# node.net
KiCad netlist of a schematic drawn in EAGLE
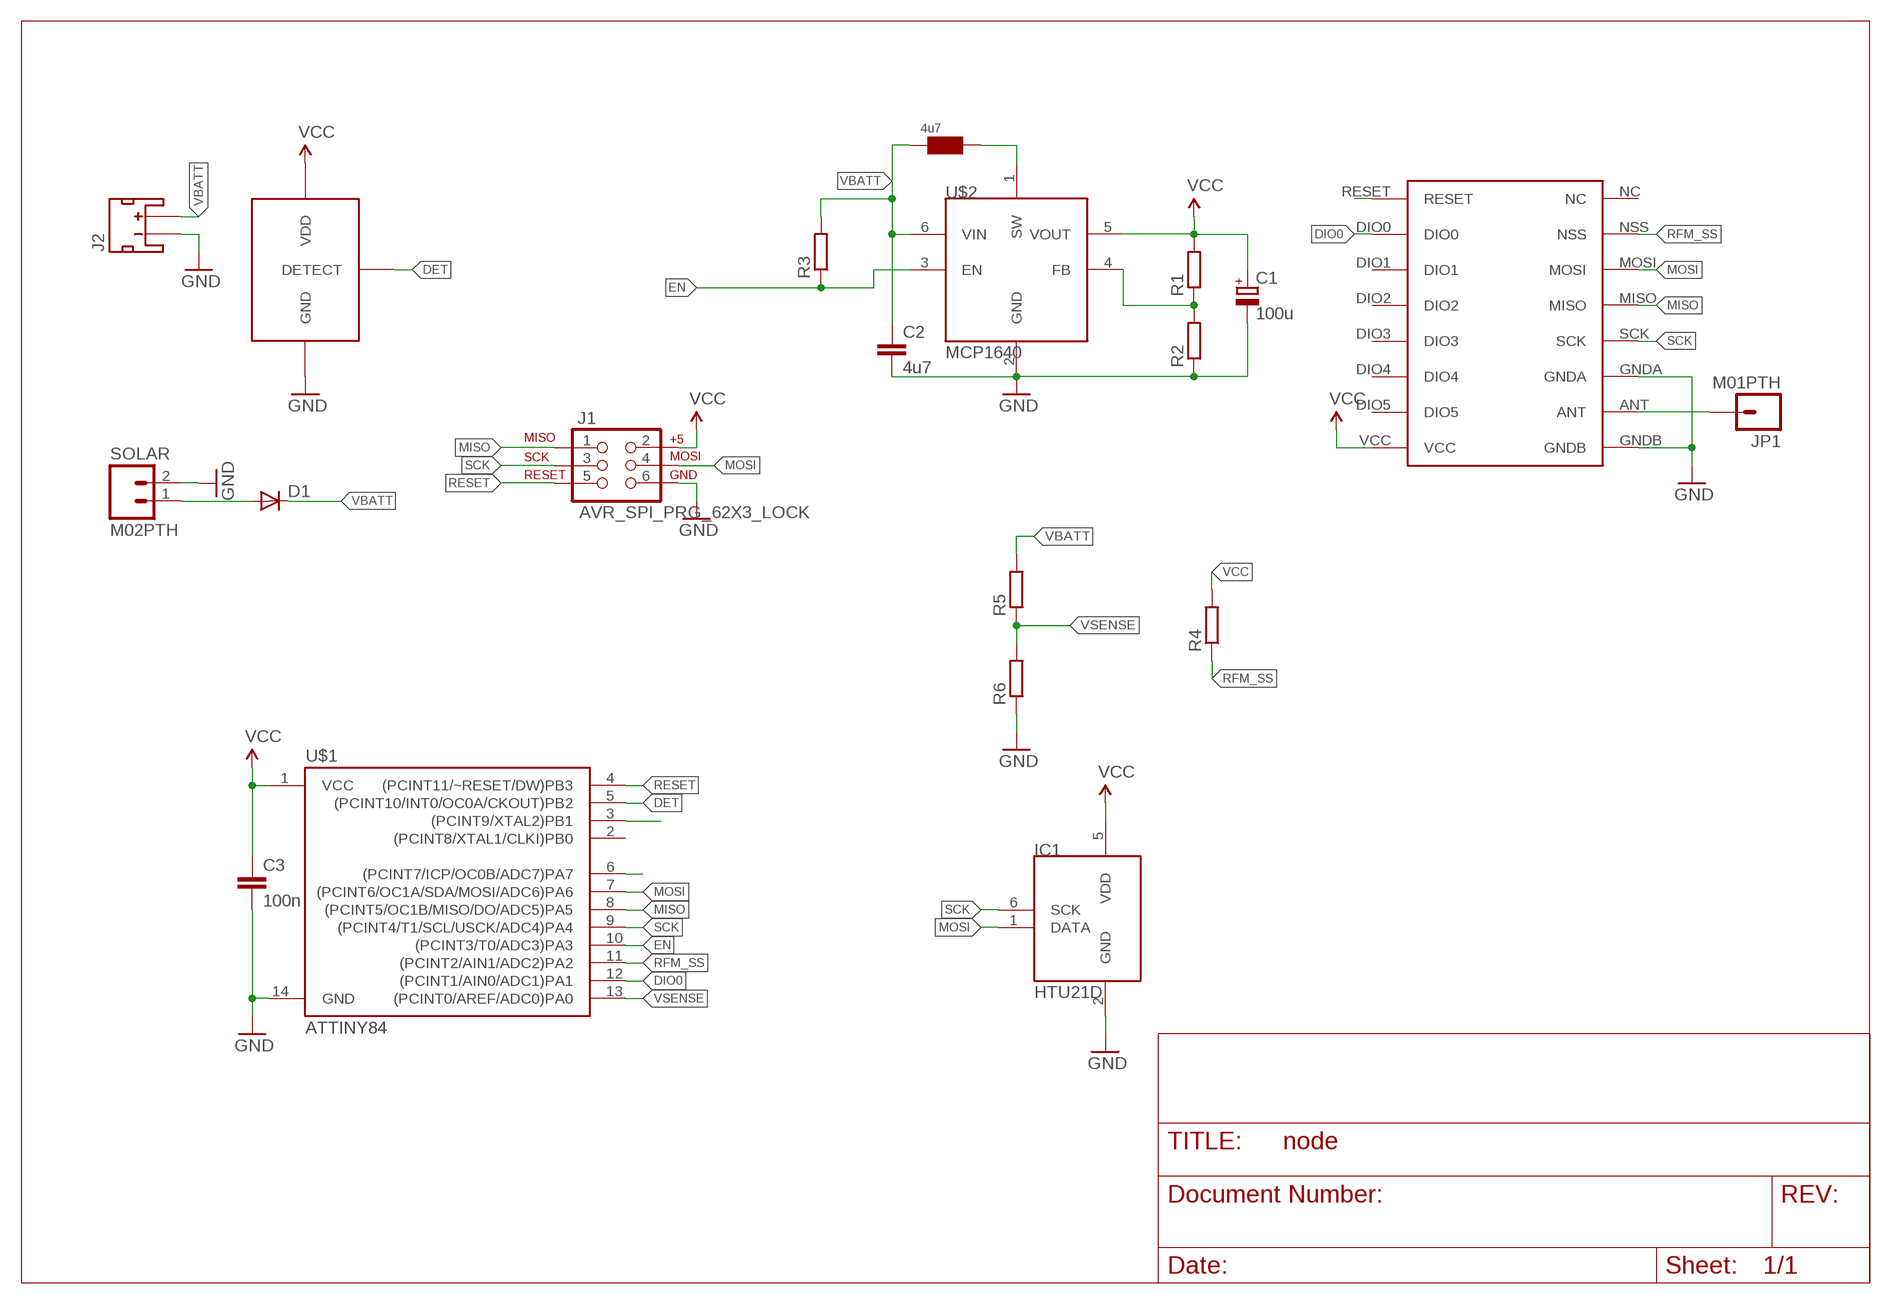
[diagram p0: schematic, sheet 1]

(export (version "E")
  (design (tool "Eeschema 10.0.6"))
  (components
    (comp (ref "C1")
      (value "100u")
      (footprint "eagle-import:SANYO-OSCON_SMD_C6")
      (libsource (lib "eagle-import") (part "CPOL-EUSANYO_SMD_C6"))
    )
    (comp (ref "C2")
      (value "4u7")
      (footprint "eagle-import:C0603")
      (libsource (lib "eagle-import") (part "C-EUC0603"))
    )
    (comp (ref "C3")
      (value "100n")
      (footprint "eagle-import:C0603")
      (libsource (lib "eagle-import") (part "C-EUC0603"))
    )
    (comp (ref "D1")
      (value "DIODE-SOD123")
      (footprint "eagle-import:SOD123")
      (libsource (lib "eagle-import") (part "DIODE-SOD123"))
    )
    (comp (ref "DF")
      (value "4u7")
      (footprint "eagle-import:BOURNS_SRN5040_L")
      (libsource (lib "eagle-import") (part "BOURNS_SRN5040"))
    )
    (comp (ref "IC1")
      (value "HTU21D")
      (footprint "eagle-import:DFN6-L")
      (libsource (lib "eagle-import") (part "HTU21D"))
    )
    (comp (ref "J1")
      (value "AVR_SPI_PRG_62X3_LOCK")
      (footprint "eagle-import:2X3_LOCK")
      (libsource (lib "eagle-import") (part "AVR_SPI_PRG_62X3_LOCK"))
    )
    (comp (ref "J2")
      (value "JST_2MM_MALE_TH")
      (footprint "eagle-import:JST-2-TH")
      (libsource (lib "eagle-import") (part "JST_2MM_MALE_TH"))
    )
    (comp (ref "JP1")
      (value "M01PTH")
      (footprint "eagle-import:1X01")
      (libsource (lib "eagle-import") (part "M01PTH"))
    )
    (comp (ref "R1")
      (value "R-EU_R0603")
      (footprint "eagle-import:R0603")
      (libsource (lib "eagle-import") (part "R-EU_R0603"))
    )
    (comp (ref "R2")
      (value "R-EU_R0603")
      (footprint "eagle-import:R0603")
      (libsource (lib "eagle-import") (part "R-EU_R0603"))
    )
    (comp (ref "R3")
      (value "R-EU_R0603")
      (footprint "eagle-import:R0603")
      (libsource (lib "eagle-import") (part "R-EU_R0603"))
    )
    (comp (ref "R4")
      (value "R-EU_R0603")
      (footprint "eagle-import:R0603")
      (libsource (lib "eagle-import") (part "R-EU_R0603"))
    )
    (comp (ref "R5")
      (value "R-EU_R0603")
      (footprint "eagle-import:R0603")
      (libsource (lib "eagle-import") (part "R-EU_R0603"))
    )
    (comp (ref "R6")
      (value "R-EU_R0603")
      (footprint "eagle-import:R0603")
      (libsource (lib "eagle-import") (part "R-EU_R0603"))
    )
    (comp (ref "SOLAR")
      (value "M02PTH")
      (footprint "eagle-import:1X02")
      (libsource (lib "eagle-import") (part "M02PTH"))
    )
    (comp (ref "U$1")
      (value "ATTINY84")
      (footprint "eagle-import:SO14")
      (libsource (lib "eagle-import") (part "ATTINY84"))
    )
    (comp (ref "U$2")
      (value "MCP1640")
      (footprint "eagle-import:SOT23-6")
      (libsource (lib "eagle-import") (part "MCP1640"))
    )
    (comp (ref "U$3")
      (value "BU49X_VDET_SOT235")
      (footprint "eagle-import:SOT23-5L")
      (libsource (lib "eagle-import") (part "BU49X_VDET_SOT235"))
    )
    (comp (ref "U$4")
      (value "RFM69HW")
      (footprint "eagle-import:RFM")
      (libsource (lib "eagle-import") (part "RFM69HW"))
    )
  )
  (nets
    (net (code "1") (name "DET") (class "Default")
      (node (ref "U$1") (pin "5") (pinfunction "(PCINT10/INT0/OC0A/CKOUT)PB2_5") (pintype "bidirectional"))
      (node (ref "U$3") (pin "1") (pinfunction "DETECT_1") (pintype "bidirectional"))
    )
    (net (code "2") (name "DIO0") (class "Default")
      (node (ref "U$1") (pin "12") (pinfunction "(PCINT1/AIN0/ADC1)PA1_12") (pintype "bidirectional"))
      (node (ref "U$4") (pin "DIO0") (pinfunction "DIO0_DIO0") (pintype "bidirectional"))
    )
    (net (code "3") (name "EN") (class "Default")
      (node (ref "R3") (pin "1") (pinfunction "1_1") (pintype "passive"))
      (node (ref "U$1") (pin "10") (pinfunction "(PCINT3/T0/ADC3)PA3_10") (pintype "bidirectional"))
      (node (ref "U$2") (pin "3") (pinfunction "EN_3") (pintype "input"))
    )
    (net (code "4") (name "GND") (class "Default")
      (node (ref "C1") (pin "-") (pinfunction "-_-") (pintype "passive"))
      (node (ref "C2") (pin "2") (pinfunction "2_2") (pintype "passive"))
      (node (ref "C3") (pin "2") (pinfunction "2_2") (pintype "passive"))
      (node (ref "IC1") (pin "2") (pinfunction "GND_2") (pintype "power_in"))
      (node (ref "J1") (pin "6") (pinfunction "6_6") (pintype "passive"))
      (node (ref "J2") (pin "2") (pinfunction "-_2") (pintype "bidirectional"))
      (node (ref "R2") (pin "1") (pinfunction "1_1") (pintype "passive"))
      (node (ref "R6") (pin "1") (pinfunction "1_1") (pintype "passive"))
      (node (ref "SOLAR") (pin "2") (pinfunction "2_2") (pintype "passive"))
      (node (ref "U$1") (pin "14") (pinfunction "GND_14") (pintype "bidirectional"))
      (node (ref "U$2") (pin "2") (pinfunction "GND_2") (pintype "power_in"))
      (node (ref "U$3") (pin "3") (pinfunction "GND_3") (pintype "bidirectional"))
      (node (ref "U$4") (pin "GNDA") (pinfunction "GNDA_GNDA") (pintype "bidirectional"))
      (node (ref "U$4") (pin "GNDB") (pinfunction "GNDB_GNDB") (pintype "bidirectional"))
    )
    (net (code "5") (name "MISO") (class "Default")
      (node (ref "J1") (pin "1") (pinfunction "1_1") (pintype "passive"))
      (node (ref "U$1") (pin "8") (pinfunction "(PCINT5/OC1B/MISO/DO/ADC5)PA5_8") (pintype "bidirectional"))
      (node (ref "U$4") (pin "MISO") (pinfunction "MISO_MISO") (pintype "bidirectional"))
    )
    (net (code "6") (name "MOSI") (class "Default")
      (node (ref "IC1") (pin "1") (pinfunction "DATA_1") (pintype "bidirectional"))
      (node (ref "J1") (pin "4") (pinfunction "4_4") (pintype "passive"))
      (node (ref "U$1") (pin "7") (pinfunction "(PCINT6/OC1A/SDA/MOSI/ADC6)PA6_7") (pintype "bidirectional"))
      (node (ref "U$4") (pin "MOSI") (pinfunction "MOSI_MOSI") (pintype "bidirectional"))
    )
    (net (code "7") (name "Net-(D1-PadA)") (class "Default")
      (node (ref "D1") (pin "A") (pinfunction "A_A") (pintype "passive"))
      (node (ref "SOLAR") (pin "1") (pinfunction "1_1") (pintype "passive"))
    )
    (net (code "8") (name "Net-(JP1-Pad1)") (class "Default")
      (node (ref "JP1") (pin "1") (pinfunction "1_1") (pintype "passive"))
      (node (ref "U$4") (pin "ANT") (pinfunction "ANT_ANT") (pintype "bidirectional"))
    )
    (net (code "9") (name "Net-(U$2-FB)") (class "Default")
      (node (ref "R1") (pin "1") (pinfunction "1_1") (pintype "passive"))
      (node (ref "R2") (pin "2") (pinfunction "2_2") (pintype "passive"))
      (node (ref "U$2") (pin "4") (pinfunction "FB_4") (pintype "input"))
    )
    (net (code "10") (name "Net-(U$2-SW)") (class "Default")
      (node (ref "DF") (pin "P$2") (pinfunction "P$2_P$2") (pintype "bidirectional"))
      (node (ref "U$2") (pin "1") (pinfunction "SW_1") (pintype "input"))
    )
    (net (code "11") (name "RESET") (class "Default")
      (node (ref "J1") (pin "5") (pinfunction "5_5") (pintype "passive"))
      (node (ref "U$1") (pin "4") (pinfunction "(PCINT11/~{RESET/DW})PB3_4") (pintype "bidirectional"))
    )
    (net (code "12") (name "RFM_SS") (class "Default")
      (node (ref "R4") (pin "1") (pinfunction "1_1") (pintype "passive"))
      (node (ref "U$1") (pin "11") (pinfunction "(PCINT2/AIN1/ADC2)PA2_11") (pintype "bidirectional"))
      (node (ref "U$4") (pin "NSS") (pinfunction "NSS_NSS") (pintype "bidirectional"))
    )
    (net (code "13") (name "SCK") (class "Default")
      (node (ref "IC1") (pin "6") (pinfunction "SCK_6") (pintype "input"))
      (node (ref "J1") (pin "3") (pinfunction "3_3") (pintype "passive"))
      (node (ref "U$1") (pin "9") (pinfunction "(PCINT4/T1/SCL/USCK/ADC4)PA4_9") (pintype "bidirectional"))
      (node (ref "U$4") (pin "SCK") (pinfunction "SCK_SCK") (pintype "bidirectional"))
    )
    (net (code "14") (name "VBATT") (class "Default")
      (node (ref "C2") (pin "1") (pinfunction "1_1") (pintype "passive"))
      (node (ref "D1") (pin "C") (pinfunction "C_C") (pintype "passive"))
      (node (ref "DF") (pin "P$1") (pinfunction "P$1_P$1") (pintype "bidirectional"))
      (node (ref "J2") (pin "1") (pinfunction "+_1") (pintype "bidirectional"))
      (node (ref "R3") (pin "2") (pinfunction "2_2") (pintype "passive"))
      (node (ref "R5") (pin "2") (pinfunction "2_2") (pintype "passive"))
      (node (ref "U$2") (pin "6") (pinfunction "VIN_6") (pintype "power_in"))
    )
    (net (code "15") (name "VCC") (class "Default")
      (node (ref "C1") (pin "+") (pinfunction "+_+") (pintype "passive"))
      (node (ref "C3") (pin "1") (pinfunction "1_1") (pintype "passive"))
      (node (ref "IC1") (pin "5") (pinfunction "VDD_5") (pintype "power_in"))
      (node (ref "J1") (pin "2") (pinfunction "2_2") (pintype "passive"))
      (node (ref "R1") (pin "2") (pinfunction "2_2") (pintype "passive"))
      (node (ref "R4") (pin "2") (pinfunction "2_2") (pintype "passive"))
      (node (ref "U$1") (pin "1") (pinfunction "VCC_1") (pintype "bidirectional"))
      (node (ref "U$2") (pin "5") (pinfunction "VOUT_5") (pintype "output"))
      (node (ref "U$3") (pin "2") (pinfunction "VDD_2") (pintype "bidirectional"))
      (node (ref "U$4") (pin "VCC") (pinfunction "VCC_VCC") (pintype "bidirectional"))
    )
    (net (code "16") (name "VSENSE") (class "Default")
      (node (ref "R5") (pin "1") (pinfunction "1_1") (pintype "passive"))
      (node (ref "R6") (pin "2") (pinfunction "2_2") (pintype "passive"))
      (node (ref "U$1") (pin "13") (pinfunction "(PCINT0/AREF/ADC0)PA0_13") (pintype "bidirectional"))
    )
    (net (code "17") (name "unconnected-(U$1-(PCINT7{slash}ICP{slash}OC0B{slash}ADC7)PA7-Pad6)") (class "Default")
      (node (ref "U$1") (pin "6") (pinfunction "(PCINT7/ICP/OC0B/ADC7)PA7_6") (pintype "bidirectional"))
    )
    (net (code "18") (name "unconnected-(U$1-(PCINT8{slash}XTAL1{slash}CLKI)PB0-Pad2)") (class "Default")
      (node (ref "U$1") (pin "2") (pinfunction "(PCINT8/XTAL1/CLKI)PB0_2") (pintype "bidirectional"))
    )
    (net (code "19") (name "unconnected-(U$1-(PCINT9{slash}XTAL2)PB1-Pad3)") (class "Default")
      (node (ref "U$1") (pin "3") (pinfunction "(PCINT9/XTAL2)PB1_3") (pintype "bidirectional"))
    )
    (net (code "20") (name "unconnected-(U$4-PadDIO1)") (class "Default")
      (node (ref "U$4") (pin "DIO1") (pinfunction "DIO1_DIO1") (pintype "bidirectional"))
    )
    (net (code "21") (name "unconnected-(U$4-PadDIO2)") (class "Default")
      (node (ref "U$4") (pin "DIO2") (pinfunction "DIO2_DIO2") (pintype "bidirectional"))
    )
    (net (code "22") (name "unconnected-(U$4-PadDIO3)") (class "Default")
      (node (ref "U$4") (pin "DIO3") (pinfunction "DIO3_DIO3") (pintype "bidirectional"))
    )
    (net (code "23") (name "unconnected-(U$4-PadDIO4)") (class "Default")
      (node (ref "U$4") (pin "DIO4") (pinfunction "DIO4_DIO4") (pintype "bidirectional"))
    )
    (net (code "24") (name "unconnected-(U$4-PadDIO5)") (class "Default")
      (node (ref "U$4") (pin "DIO5") (pinfunction "DIO5_DIO5") (pintype "bidirectional"))
    )
    (net (code "25") (name "unconnected-(U$4-PadNC)") (class "Default")
      (node (ref "U$4") (pin "NC") (pinfunction "NC_NC") (pintype "bidirectional"))
    )
    (net (code "26") (name "unconnected-(U$4-PadRESET)") (class "Default")
      (node (ref "U$4") (pin "RESET") (pinfunction "RESET_RESET") (pintype "bidirectional"))
    )
  )
)
